# can-weichendecoder-magnet.net
KiCad netlist of a schematic drawn in EAGLE
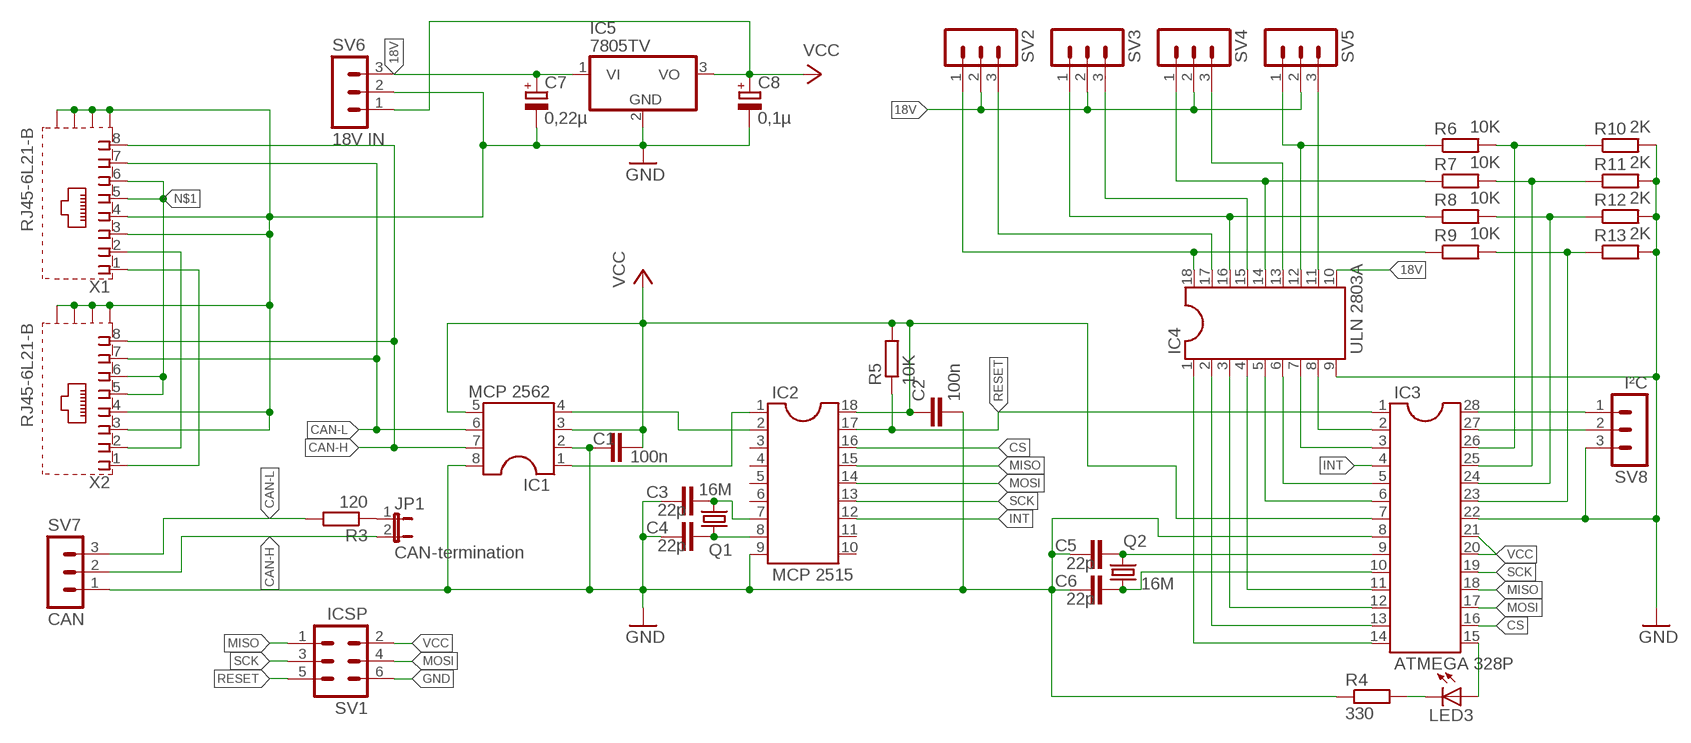
[diagram p0: schematic, sheet 1]

(export (version "E")
  (design (tool "Eeschema 10.0.6"))
  (components
    (comp (ref "C1")
      (value "100n")
      (footprint "eagle-import:C2.5-2")
      (libsource (lib "eagle-import") (part "C2.5/2"))
    )
    (comp (ref "C2")
      (value "100n")
      (footprint "eagle-import:C2.5-2")
      (libsource (lib "eagle-import") (part "C2.5/2"))
    )
    (comp (ref "C3")
      (value "22p")
      (footprint "eagle-import:C2.5-2")
      (libsource (lib "eagle-import") (part "C2.5/2"))
    )
    (comp (ref "C4")
      (value "22p")
      (footprint "eagle-import:C2.5-2")
      (libsource (lib "eagle-import") (part "C2.5/2"))
    )
    (comp (ref "C5")
      (value "22p")
      (footprint "eagle-import:C2.5-2")
      (libsource (lib "eagle-import") (part "C2.5/2"))
    )
    (comp (ref "C6")
      (value "22p")
      (footprint "eagle-import:C2.5-2")
      (libsource (lib "eagle-import") (part "C2.5/2"))
    )
    (comp (ref "C7")
      (value "0,22µ")
      (footprint "eagle-import:E2,5-6")
      (libsource (lib "eagle-import") (part "CPOL-EUE2.5-6"))
    )
    (comp (ref "C8")
      (value "0,1µ")
      (footprint "eagle-import:E2,5-6")
      (libsource (lib "eagle-import") (part "CPOL-EUE2.5-6"))
    )
    (comp (ref "IC1")
      (value "MCP 2562")
      (footprint "eagle-import:SOCKET-08")
      (libsource (lib "eagle-import") (part "DIL8S"))
    )
    (comp (ref "IC2")
      (value "MCP 2515")
      (footprint "eagle-import:SOCKET-18")
      (libsource (lib "eagle-import") (part "DIL18S"))
    )
    (comp (ref "IC3")
      (value "ATMEGA 328P")
      (footprint "eagle-import:DIL28-3")
      (libsource (lib "eagle-import") (part "DIL28-3"))
    )
    (comp (ref "IC4")
      (value "ULN 2803A")
      (footprint "eagle-import:SOCKET-18")
      (libsource (lib "eagle-import") (part "DIL18S"))
    )
    (comp (ref "IC5")
      (value "7805TV")
      (footprint "eagle-import:TO220V")
      (libsource (lib "eagle-import") (part "78TV05"))
    )
    (comp (ref "JP1")
      (value "CAN-termination")
      (footprint "eagle-import:JP1")
      (libsource (lib "eagle-import") (part "JP1E"))
    )
    (comp (ref "LED3")
      (value "LED5MM")
      (footprint "eagle-import:LED5MM")
      (libsource (lib "eagle-import") (part "LED5MM"))
    )
    (comp (ref "Q1")
      (value "16M")
      (footprint "eagle-import:HC49_S")
      (libsource (lib "eagle-import") (part "CRYSTALHC49S"))
    )
    (comp (ref "Q2")
      (value "16M")
      (footprint "eagle-import:HC49_S")
      (libsource (lib "eagle-import") (part "CRYSTALHC49S"))
    )
    (comp (ref "R3")
      (value "120")
      (footprint "eagle-import:0207_10")
      (libsource (lib "eagle-import") (part "R-EU_0207/10"))
    )
    (comp (ref "R4")
      (value "330")
      (footprint "eagle-import:0207_10")
      (libsource (lib "eagle-import") (part "R-EU_0207/10"))
    )
    (comp (ref "R5")
      (value "10K")
      (footprint "eagle-import:0207_10")
      (libsource (lib "eagle-import") (part "R-EU_0207/10"))
    )
    (comp (ref "R6")
      (value "10K")
      (footprint "eagle-import:0207_10")
      (libsource (lib "eagle-import") (part "R-EU_0207/10"))
    )
    (comp (ref "R7")
      (value "10K")
      (footprint "eagle-import:0207_10")
      (libsource (lib "eagle-import") (part "R-EU_0207/10"))
    )
    (comp (ref "R8")
      (value "10K")
      (footprint "eagle-import:0207_10")
      (libsource (lib "eagle-import") (part "R-EU_0207/10"))
    )
    (comp (ref "R9")
      (value "10K")
      (footprint "eagle-import:0207_10")
      (libsource (lib "eagle-import") (part "R-EU_0207/10"))
    )
    (comp (ref "R10")
      (value "2K")
      (footprint "eagle-import:0207_10")
      (libsource (lib "eagle-import") (part "R-EU_0207/10"))
    )
    (comp (ref "R11")
      (value "2K")
      (footprint "eagle-import:0207_10")
      (libsource (lib "eagle-import") (part "R-EU_0207/10"))
    )
    (comp (ref "R12")
      (value "2K")
      (footprint "eagle-import:0207_10")
      (libsource (lib "eagle-import") (part "R-EU_0207/10"))
    )
    (comp (ref "R13")
      (value "2K")
      (footprint "eagle-import:0207_10")
      (libsource (lib "eagle-import") (part "R-EU_0207/10"))
    )
    (comp (ref "SV1")
      (value "ICSP")
      (footprint "eagle-import:MA03-2")
      (libsource (lib "eagle-import") (part "MA03-2"))
    )
    (comp (ref "SV2")
      (value "MA03-1")
      (footprint "eagle-import:MA03-1")
      (libsource (lib "eagle-import") (part "MA03-1"))
    )
    (comp (ref "SV3")
      (value "MA03-1")
      (footprint "eagle-import:MA03-1")
      (libsource (lib "eagle-import") (part "MA03-1"))
    )
    (comp (ref "SV4")
      (value "MA03-1")
      (footprint "eagle-import:MA03-1")
      (libsource (lib "eagle-import") (part "MA03-1"))
    )
    (comp (ref "SV5")
      (value "MA03-1")
      (footprint "eagle-import:MA03-1")
      (libsource (lib "eagle-import") (part "MA03-1"))
    )
    (comp (ref "SV6")
      (value "18V IN")
      (footprint "eagle-import:MA03-1")
      (libsource (lib "eagle-import") (part "MA03-1"))
    )
    (comp (ref "SV7")
      (value "CAN")
      (footprint "eagle-import:MA03-1")
      (libsource (lib "eagle-import") (part "MA03-1"))
    )
    (comp (ref "SV8")
      (value "I²C")
      (footprint "eagle-import:MA03-1")
      (libsource (lib "eagle-import") (part "MA03-1"))
    )
    (comp (ref "X1")
      (value "RJ45-6L21-B")
      (footprint "eagle-import:RJ45-SHIELD1")
      (libsource (lib "eagle-import") (part "RJ4521-B-6L"))
    )
    (comp (ref "X2")
      (value "RJ45-6L21-B")
      (footprint "eagle-import:RJ45-SHIELD1")
      (libsource (lib "eagle-import") (part "RJ4521-B-6L"))
    )
  )
  (nets
    (net (code "1") (name "18V") (class "Default")
      (node (ref "C7") (pin "+") (pinfunction "+_+") (pintype "passive"))
      (node (ref "IC4") (pin "10") (pinfunction "10_10") (pintype "passive"))
      (node (ref "IC5") (pin "1") (pinfunction "VI_1") (pintype "input"))
      (node (ref "SV2") (pin "2") (pinfunction "2_2") (pintype "passive"))
      (node (ref "SV3") (pin "2") (pinfunction "2_2") (pintype "passive"))
      (node (ref "SV4") (pin "2") (pinfunction "2_2") (pintype "passive"))
      (node (ref "SV5") (pin "2") (pinfunction "2_2") (pintype "passive"))
      (node (ref "SV6") (pin "3") (pinfunction "3_3") (pintype "passive"))
    )
    (net (code "2") (name "CAN-H") (class "Default")
      (node (ref "IC1") (pin "7") (pinfunction "7_7") (pintype "passive"))
      (node (ref "JP1") (pin "2") (pinfunction "2_2") (pintype "passive"))
      (node (ref "SV7") (pin "2") (pinfunction "2_2") (pintype "passive"))
      (node (ref "X1") (pin "8") (pinfunction "8_8") (pintype "passive"))
      (node (ref "X2") (pin "8") (pinfunction "8_8") (pintype "passive"))
    )
    (net (code "3") (name "CAN-L") (class "Default")
      (node (ref "IC1") (pin "6") (pinfunction "6_6") (pintype "passive"))
      (node (ref "R3") (pin "2") (pinfunction "2_2") (pintype "passive"))
      (node (ref "SV7") (pin "3") (pinfunction "3_3") (pintype "passive"))
      (node (ref "X1") (pin "7") (pinfunction "7_7") (pintype "passive"))
      (node (ref "X2") (pin "7") (pinfunction "7_7") (pintype "passive"))
    )
    (net (code "4") (name "CS") (class "Default")
      (node (ref "IC2") (pin "16") (pinfunction "16_16") (pintype "passive"))
      (node (ref "IC3") (pin "16") (pinfunction "16_16") (pintype "passive"))
    )
    (net (code "5") (name "GND") (class "Default")
      (node (ref "C1") (pin "1") (pinfunction "1_1") (pintype "passive"))
      (node (ref "C2") (pin "2") (pinfunction "2_2") (pintype "passive"))
      (node (ref "C3") (pin "1") (pinfunction "1_1") (pintype "passive"))
      (node (ref "C4") (pin "1") (pinfunction "1_1") (pintype "passive"))
      (node (ref "C5") (pin "1") (pinfunction "1_1") (pintype "passive"))
      (node (ref "C6") (pin "1") (pinfunction "1_1") (pintype "passive"))
      (node (ref "C7") (pin "-") (pinfunction "-_-") (pintype "passive"))
      (node (ref "C8") (pin "-") (pinfunction "-_-") (pintype "passive"))
      (node (ref "IC1") (pin "2") (pinfunction "2_2") (pintype "passive"))
      (node (ref "IC1") (pin "8") (pinfunction "8_8") (pintype "passive"))
      (node (ref "IC2") (pin "9") (pinfunction "9_9") (pintype "passive"))
      (node (ref "IC3") (pin "22") (pinfunction "22_22") (pintype "passive"))
      (node (ref "IC3") (pin "8") (pinfunction "8_8") (pintype "passive"))
      (node (ref "IC4") (pin "9") (pinfunction "9_9") (pintype "passive"))
      (node (ref "IC5") (pin "2") (pinfunction "GND_2") (pintype "passive"))
      (node (ref "R10") (pin "2") (pinfunction "2_2") (pintype "passive"))
      (node (ref "R11") (pin "2") (pinfunction "2_2") (pintype "passive"))
      (node (ref "R12") (pin "2") (pinfunction "2_2") (pintype "passive"))
      (node (ref "R13") (pin "2") (pinfunction "2_2") (pintype "passive"))
      (node (ref "R4") (pin "1") (pinfunction "1_1") (pintype "passive"))
      (node (ref "SV1") (pin "6") (pinfunction "6_6") (pintype "passive"))
      (node (ref "SV6") (pin "2") (pinfunction "2_2") (pintype "passive"))
      (node (ref "SV7") (pin "1") (pinfunction "1_1") (pintype "passive"))
      (node (ref "SV8") (pin "3") (pinfunction "3_3") (pintype "passive"))
      (node (ref "X1") (pin "3") (pinfunction "3_3") (pintype "passive"))
      (node (ref "X1") (pin "4") (pinfunction "4_4") (pintype "passive"))
      (node (ref "X1") (pin "S1") (pinfunction "S_S1") (pintype "passive"))
      (node (ref "X1") (pin "S2") (pinfunction "S_S2") (pintype "passive"))
      (node (ref "X1") (pin "S3") (pinfunction "S_S3") (pintype "passive"))
      (node (ref "X1") (pin "S4") (pinfunction "S_S4") (pintype "passive"))
      (node (ref "X2") (pin "3") (pinfunction "3_3") (pintype "passive"))
      (node (ref "X2") (pin "4") (pinfunction "4_4") (pintype "passive"))
      (node (ref "X2") (pin "S1") (pinfunction "S_S1") (pintype "passive"))
      (node (ref "X2") (pin "S2") (pinfunction "S_S2") (pintype "passive"))
      (node (ref "X2") (pin "S3") (pinfunction "S_S3") (pintype "passive"))
      (node (ref "X2") (pin "S4") (pinfunction "S_S4") (pintype "passive"))
    )
    (net (code "6") (name "INT") (class "Default")
      (node (ref "IC2") (pin "12") (pinfunction "12_12") (pintype "passive"))
      (node (ref "IC3") (pin "4") (pinfunction "4_4") (pintype "passive"))
    )
    (net (code "7") (name "MISO") (class "Default")
      (node (ref "IC2") (pin "15") (pinfunction "15_15") (pintype "passive"))
      (node (ref "IC3") (pin "18") (pinfunction "18_18") (pintype "passive"))
      (node (ref "SV1") (pin "1") (pinfunction "1_1") (pintype "passive"))
    )
    (net (code "8") (name "MOSI") (class "Default")
      (node (ref "IC2") (pin "14") (pinfunction "14_14") (pintype "passive"))
      (node (ref "IC3") (pin "17") (pinfunction "17_17") (pintype "passive"))
      (node (ref "SV1") (pin "4") (pinfunction "4_4") (pintype "passive"))
    )
    (net (code "9") (name "N$1") (class "Default")
      (node (ref "X1") (pin "5") (pinfunction "5_5") (pintype "passive"))
      (node (ref "X1") (pin "6") (pinfunction "6_6") (pintype "passive"))
      (node (ref "X2") (pin "5") (pinfunction "5_5") (pintype "passive"))
      (node (ref "X2") (pin "6") (pinfunction "6_6") (pintype "passive"))
    )
    (net (code "10") (name "Net-(C3-Pad2)") (class "Default")
      (node (ref "C3") (pin "2") (pinfunction "2_2") (pintype "passive"))
      (node (ref "IC2") (pin "7") (pinfunction "7_7") (pintype "passive"))
      (node (ref "Q1") (pin "2") (pinfunction "2_2") (pintype "passive"))
    )
    (net (code "11") (name "Net-(C4-Pad2)") (class "Default")
      (node (ref "C4") (pin "2") (pinfunction "2_2") (pintype "passive"))
      (node (ref "IC2") (pin "8") (pinfunction "8_8") (pintype "passive"))
      (node (ref "Q1") (pin "1") (pinfunction "1_1") (pintype "passive"))
    )
    (net (code "12") (name "Net-(C5-Pad2)") (class "Default")
      (node (ref "C5") (pin "2") (pinfunction "2_2") (pintype "passive"))
      (node (ref "IC3") (pin "9") (pinfunction "9_9") (pintype "passive"))
      (node (ref "Q2") (pin "2") (pinfunction "2_2") (pintype "passive"))
    )
    (net (code "13") (name "Net-(C6-Pad2)") (class "Default")
      (node (ref "C6") (pin "2") (pinfunction "2_2") (pintype "passive"))
      (node (ref "IC3") (pin "10") (pinfunction "10_10") (pintype "passive"))
      (node (ref "Q2") (pin "1") (pinfunction "1_1") (pintype "passive"))
    )
    (net (code "14") (name "Net-(IC1-Pad1)") (class "Default")
      (node (ref "IC1") (pin "1") (pinfunction "1_1") (pintype "passive"))
      (node (ref "IC2") (pin "1") (pinfunction "1_1") (pintype "passive"))
    )
    (net (code "15") (name "Net-(IC1-Pad4)") (class "Default")
      (node (ref "IC1") (pin "4") (pinfunction "4_4") (pintype "passive"))
      (node (ref "IC2") (pin "2") (pinfunction "2_2") (pintype "passive"))
    )
    (net (code "16") (name "Net-(IC3-Pad2)") (class "Default")
      (node (ref "IC3") (pin "2") (pinfunction "2_2") (pintype "passive"))
      (node (ref "IC4") (pin "8") (pinfunction "8_8") (pintype "passive"))
    )
    (net (code "17") (name "Net-(IC3-Pad3)") (class "Default")
      (node (ref "IC3") (pin "3") (pinfunction "3_3") (pintype "passive"))
      (node (ref "IC4") (pin "7") (pinfunction "7_7") (pintype "passive"))
    )
    (net (code "18") (name "Net-(IC3-Pad5)") (class "Default")
      (node (ref "IC3") (pin "5") (pinfunction "5_5") (pintype "passive"))
      (node (ref "IC4") (pin "6") (pinfunction "6_6") (pintype "passive"))
    )
    (net (code "19") (name "Net-(IC3-Pad6)") (class "Default")
      (node (ref "IC3") (pin "6") (pinfunction "6_6") (pintype "passive"))
      (node (ref "IC4") (pin "5") (pinfunction "5_5") (pintype "passive"))
    )
    (net (code "20") (name "Net-(IC3-Pad11)") (class "Default")
      (node (ref "IC3") (pin "11") (pinfunction "11_11") (pintype "passive"))
      (node (ref "IC4") (pin "4") (pinfunction "4_4") (pintype "passive"))
    )
    (net (code "21") (name "Net-(IC3-Pad12)") (class "Default")
      (node (ref "IC3") (pin "12") (pinfunction "12_12") (pintype "passive"))
      (node (ref "IC4") (pin "3") (pinfunction "3_3") (pintype "passive"))
    )
    (net (code "22") (name "Net-(IC3-Pad13)") (class "Default")
      (node (ref "IC3") (pin "13") (pinfunction "13_13") (pintype "passive"))
      (node (ref "IC4") (pin "2") (pinfunction "2_2") (pintype "passive"))
    )
    (net (code "23") (name "Net-(IC3-Pad14)") (class "Default")
      (node (ref "IC3") (pin "14") (pinfunction "14_14") (pintype "passive"))
      (node (ref "IC4") (pin "1") (pinfunction "1_1") (pintype "passive"))
    )
    (net (code "24") (name "Net-(IC3-Pad15)") (class "Default")
      (node (ref "IC3") (pin "15") (pinfunction "15_15") (pintype "passive"))
      (node (ref "LED3") (pin "A") (pinfunction "A_A") (pintype "passive"))
    )
    (net (code "25") (name "Net-(IC3-Pad23)") (class "Default")
      (node (ref "IC3") (pin "23") (pinfunction "23_23") (pintype "passive"))
      (node (ref "R13") (pin "1") (pinfunction "1_1") (pintype "passive"))
      (node (ref "R9") (pin "2") (pinfunction "2_2") (pintype "passive"))
    )
    (net (code "26") (name "Net-(IC3-Pad24)") (class "Default")
      (node (ref "IC3") (pin "24") (pinfunction "24_24") (pintype "passive"))
      (node (ref "R12") (pin "1") (pinfunction "1_1") (pintype "passive"))
      (node (ref "R8") (pin "2") (pinfunction "2_2") (pintype "passive"))
    )
    (net (code "27") (name "Net-(IC3-Pad25)") (class "Default")
      (node (ref "IC3") (pin "25") (pinfunction "25_25") (pintype "passive"))
      (node (ref "R11") (pin "1") (pinfunction "1_1") (pintype "passive"))
      (node (ref "R7") (pin "2") (pinfunction "2_2") (pintype "passive"))
    )
    (net (code "28") (name "Net-(IC3-Pad26)") (class "Default")
      (node (ref "IC3") (pin "26") (pinfunction "26_26") (pintype "passive"))
      (node (ref "R10") (pin "1") (pinfunction "1_1") (pintype "passive"))
      (node (ref "R6") (pin "2") (pinfunction "2_2") (pintype "passive"))
    )
    (net (code "29") (name "Net-(IC3-Pad27)") (class "Default")
      (node (ref "IC3") (pin "27") (pinfunction "27_27") (pintype "passive"))
      (node (ref "SV8") (pin "2") (pinfunction "2_2") (pintype "passive"))
    )
    (net (code "30") (name "Net-(IC3-Pad28)") (class "Default")
      (node (ref "IC3") (pin "28") (pinfunction "28_28") (pintype "passive"))
      (node (ref "SV8") (pin "1") (pinfunction "1_1") (pintype "passive"))
    )
    (net (code "31") (name "Net-(IC4-Pad11)") (class "Default")
      (node (ref "IC4") (pin "11") (pinfunction "11_11") (pintype "passive"))
      (node (ref "SV5") (pin "3") (pinfunction "3_3") (pintype "passive"))
    )
    (net (code "32") (name "Net-(IC4-Pad12)") (class "Default")
      (node (ref "IC4") (pin "12") (pinfunction "12_12") (pintype "passive"))
      (node (ref "R6") (pin "1") (pinfunction "1_1") (pintype "passive"))
      (node (ref "SV5") (pin "1") (pinfunction "1_1") (pintype "passive"))
    )
    (net (code "33") (name "Net-(IC4-Pad13)") (class "Default")
      (node (ref "IC4") (pin "13") (pinfunction "13_13") (pintype "passive"))
      (node (ref "SV4") (pin "3") (pinfunction "3_3") (pintype "passive"))
    )
    (net (code "34") (name "Net-(IC4-Pad14)") (class "Default")
      (node (ref "IC4") (pin "14") (pinfunction "14_14") (pintype "passive"))
      (node (ref "R7") (pin "1") (pinfunction "1_1") (pintype "passive"))
      (node (ref "SV4") (pin "1") (pinfunction "1_1") (pintype "passive"))
    )
    (net (code "35") (name "Net-(IC4-Pad15)") (class "Default")
      (node (ref "IC4") (pin "15") (pinfunction "15_15") (pintype "passive"))
      (node (ref "SV3") (pin "3") (pinfunction "3_3") (pintype "passive"))
    )
    (net (code "36") (name "Net-(IC4-Pad16)") (class "Default")
      (node (ref "IC4") (pin "16") (pinfunction "16_16") (pintype "passive"))
      (node (ref "R8") (pin "1") (pinfunction "1_1") (pintype "passive"))
      (node (ref "SV3") (pin "1") (pinfunction "1_1") (pintype "passive"))
    )
    (net (code "37") (name "Net-(IC4-Pad17)") (class "Default")
      (node (ref "IC4") (pin "17") (pinfunction "17_17") (pintype "passive"))
      (node (ref "SV2") (pin "3") (pinfunction "3_3") (pintype "passive"))
    )
    (net (code "38") (name "Net-(IC4-Pad18)") (class "Default")
      (node (ref "IC4") (pin "18") (pinfunction "18_18") (pintype "passive"))
      (node (ref "R9") (pin "1") (pinfunction "1_1") (pintype "passive"))
      (node (ref "SV2") (pin "1") (pinfunction "1_1") (pintype "passive"))
    )
    (net (code "39") (name "Net-(JP1-Pad1)") (class "Default")
      (node (ref "JP1") (pin "1") (pinfunction "1_1") (pintype "passive"))
      (node (ref "R3") (pin "1") (pinfunction "1_1") (pintype "passive"))
    )
    (net (code "40") (name "Net-(LED3-C)") (class "Default")
      (node (ref "LED3") (pin "K") (pinfunction "C_K") (pintype "passive"))
      (node (ref "R4") (pin "2") (pinfunction "2_2") (pintype "passive"))
    )
    (net (code "41") (name "Net-(X1-Pad1)") (class "Default")
      (node (ref "X1") (pin "1") (pinfunction "1_1") (pintype "passive"))
      (node (ref "X2") (pin "1") (pinfunction "1_1") (pintype "passive"))
    )
    (net (code "42") (name "Net-(X1-Pad2)") (class "Default")
      (node (ref "X1") (pin "2") (pinfunction "2_2") (pintype "passive"))
      (node (ref "X2") (pin "2") (pinfunction "2_2") (pintype "passive"))
    )
    (net (code "43") (name "RESET") (class "Default")
      (node (ref "IC2") (pin "17") (pinfunction "17_17") (pintype "passive"))
      (node (ref "IC3") (pin "1") (pinfunction "1_1") (pintype "passive"))
      (node (ref "R5") (pin "1") (pinfunction "1_1") (pintype "passive"))
      (node (ref "SV1") (pin "5") (pinfunction "5_5") (pintype "passive"))
    )
    (net (code "44") (name "SCK") (class "Default")
      (node (ref "IC2") (pin "13") (pinfunction "13_13") (pintype "passive"))
      (node (ref "IC3") (pin "19") (pinfunction "19_19") (pintype "passive"))
      (node (ref "SV1") (pin "3") (pinfunction "3_3") (pintype "passive"))
    )
    (net (code "45") (name "VCC") (class "Default")
      (node (ref "C1") (pin "2") (pinfunction "2_2") (pintype "passive"))
      (node (ref "C2") (pin "1") (pinfunction "1_1") (pintype "passive"))
      (node (ref "C8") (pin "+") (pinfunction "+_+") (pintype "passive"))
      (node (ref "IC1") (pin "3") (pinfunction "3_3") (pintype "passive"))
      (node (ref "IC1") (pin "5") (pinfunction "5_5") (pintype "passive"))
      (node (ref "IC2") (pin "18") (pinfunction "18_18") (pintype "passive"))
      (node (ref "IC3") (pin "20") (pinfunction "20_20") (pintype "passive"))
      (node (ref "IC3") (pin "21") (pinfunction "21_21") (pintype "passive"))
      (node (ref "IC3") (pin "7") (pinfunction "7_7") (pintype "passive"))
      (node (ref "IC5") (pin "3") (pinfunction "VO_3") (pintype "passive"))
      (node (ref "R5") (pin "2") (pinfunction "2_2") (pintype "passive"))
      (node (ref "SV1") (pin "2") (pinfunction "2_2") (pintype "passive"))
      (node (ref "SV6") (pin "1") (pinfunction "1_1") (pintype "passive"))
    )
    (net (code "46") (name "unconnected-(IC2-Pad3)") (class "Default")
      (node (ref "IC2") (pin "3") (pinfunction "3_3") (pintype "passive"))
    )
    (net (code "47") (name "unconnected-(IC2-Pad4)") (class "Default")
      (node (ref "IC2") (pin "4") (pinfunction "4_4") (pintype "passive"))
    )
    (net (code "48") (name "unconnected-(IC2-Pad5)") (class "Default")
      (node (ref "IC2") (pin "5") (pinfunction "5_5") (pintype "passive"))
    )
    (net (code "49") (name "unconnected-(IC2-Pad6)") (class "Default")
      (node (ref "IC2") (pin "6") (pinfunction "6_6") (pintype "passive"))
    )
    (net (code "50") (name "unconnected-(IC2-Pad10)") (class "Default")
      (node (ref "IC2") (pin "10") (pinfunction "10_10") (pintype "passive"))
    )
    (net (code "51") (name "unconnected-(IC2-Pad11)") (class "Default")
      (node (ref "IC2") (pin "11") (pinfunction "11_11") (pintype "passive"))
    )
  )
)
